# Galaxy.net
KiCad netlist of a schematic drawn in Altium Designer
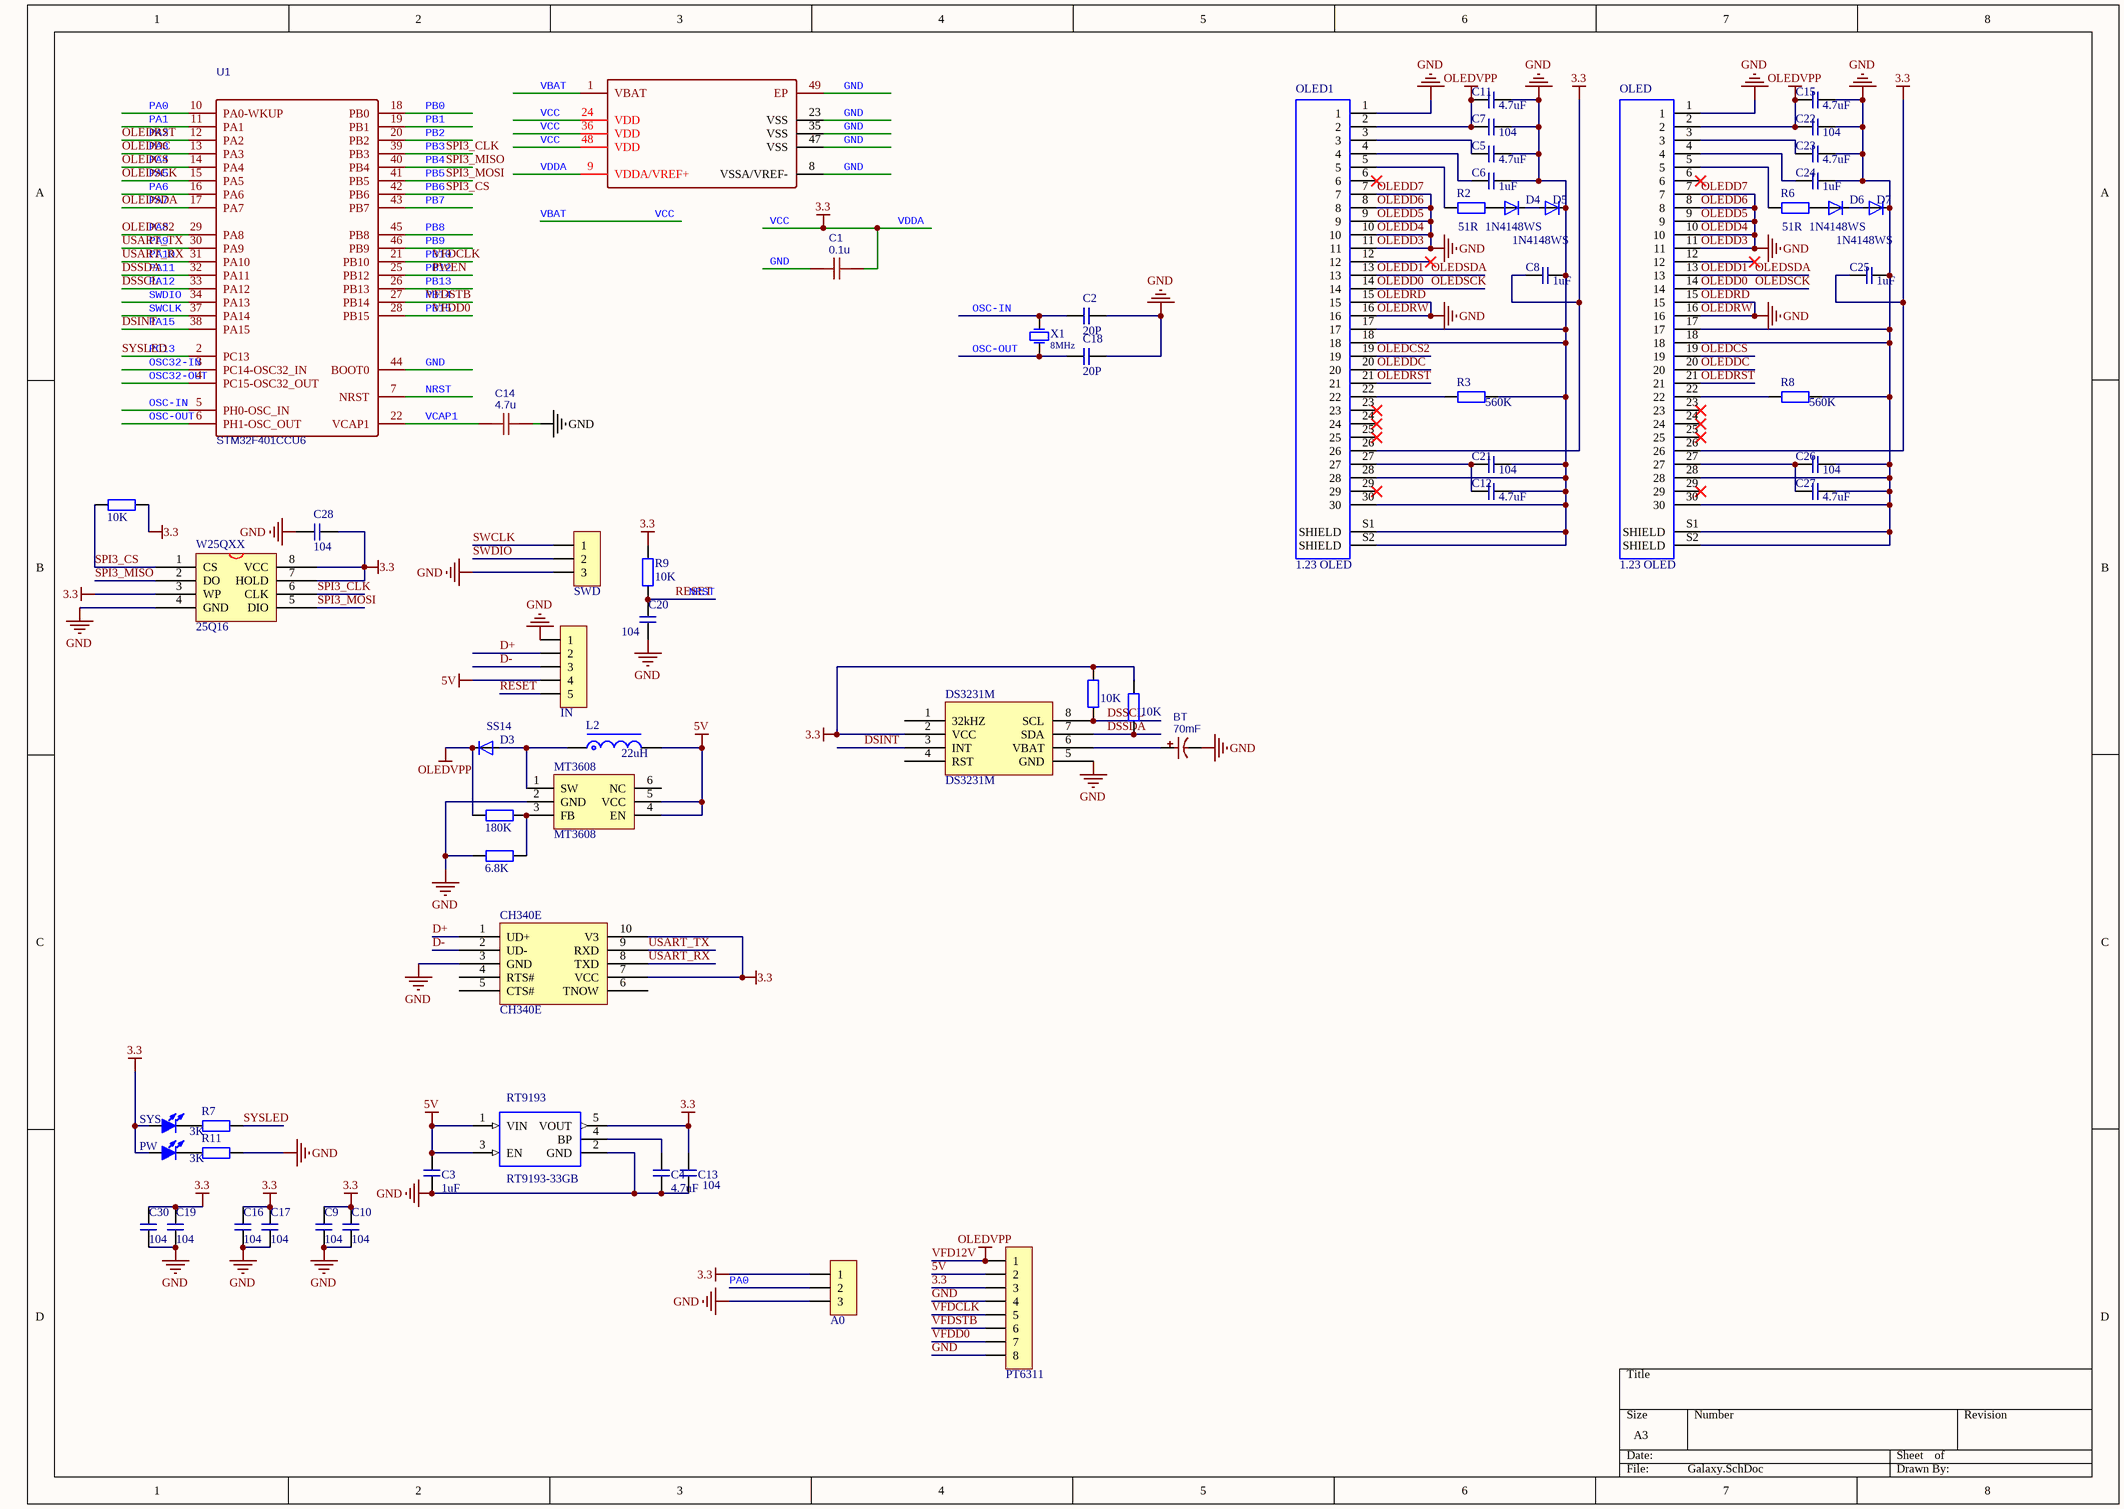
[diagram p0: Galaxy.SchDoc]

(export (version "E")
  (design (tool "Eeschema 10.0.6"))
  (components
    (comp (ref "A0")
      (value "HDR-1X3")
      (footprint "ZH1.5-WS-3P")
      (description "3P接插件")
      (fields (field (name "版权归属") "源创客"))
      (libsource (lib "4.3   - 接插件-脚距1.5") (part "Header 3"))
    )
    (comp (ref "BT")
      (value "70mF")
      (footprint "CAP-TH_BD4.8-P3.95_SM3R3703T01")
      (fields
        (field (name "BOM_SUPPLIER PART") "C132600")
        (field (name "BOM_MANUFACTURER PART") "SM3R3703T01")
        (field (name "CONTRIBUTOR") "LCSC")
      )
      (libsource (lib "altium-import") (part "root_0_70mF_"))
    )
    (comp (ref "C1")
      (value "0.1u")
      (footprint "0603C")
      (fields (field (name "CONTRIBUTOR") "LCEDA_Lib"))
      (libsource (lib "altium-import") (part "root_2_0.1u_"))
    )
    (comp (ref "C2") (value "20P") (footprint "0603C") (libsource (lib "Schlib1") (part "电容")))
    (comp (ref "C3") (value "1uF") (footprint "0603C") (libsource (lib "Schlib1") (part "电容")))
    (comp (ref "C4") (value "4.7uF") (footprint "0603C") (libsource (lib "Schlib1") (part "电容")))
    (comp (ref "C5") (value "4.7uF") (footprint "0603C") (libsource (lib "Schlib1") (part "电容")))
    (comp (ref "C6") (value "1uF") (footprint "0603C") (libsource (lib "Schlib1") (part "电容")))
    (comp (ref "C7") (value "104") (footprint "0603C") (libsource (lib "Schlib1") (part "电容")))
    (comp (ref "C8") (value "1uF") (footprint "0603C") (libsource (lib "Schlib1") (part "电容")))
    (comp (ref "C9") (value "104") (footprint "0603C") (libsource (lib "Schlib1") (part "电容")))
    (comp (ref "C10") (value "104") (footprint "0603C") (libsource (lib "Schlib1") (part "电容")))
    (comp (ref "C11") (value "4.7uF") (footprint "0603C") (libsource (lib "Schlib1") (part "电容")))
    (comp (ref "C12") (value "4.7uF") (footprint "0603C") (libsource (lib "Schlib1") (part "电容")))
    (comp (ref "C13") (value "104") (footprint "0603C") (libsource (lib "Schlib1") (part "电容")))
    (comp (ref "C14")
      (value "4.7u")
      (footprint "0603C")
      (fields (field (name "CONTRIBUTOR") "LCEDA_Lib"))
      (libsource (lib "altium-import") (part "root_0_4.7u_"))
    )
    (comp (ref "C15") (value "4.7uF") (footprint "0603C") (libsource (lib "Schlib1") (part "电容")))
    (comp (ref "C16") (value "104") (footprint "0603C") (libsource (lib "Schlib1") (part "电容")))
    (comp (ref "C17") (value "104") (footprint "0603C") (libsource (lib "Schlib1") (part "电容")))
    (comp (ref "C18") (value "20P") (footprint "0603C") (libsource (lib "Schlib1") (part "电容")))
    (comp (ref "C19") (value "104") (footprint "0603C") (libsource (lib "Schlib1") (part "电容")))
    (comp (ref "C20") (value "104") (footprint "0603C") (libsource (lib "Schlib1") (part "电容")))
    (comp (ref "C21") (value "104") (footprint "0603C") (libsource (lib "Schlib1") (part "电容")))
    (comp (ref "C22") (value "104") (footprint "0603C") (libsource (lib "Schlib1") (part "电容")))
    (comp (ref "C23") (value "4.7uF") (footprint "0603C") (libsource (lib "Schlib1") (part "电容")))
    (comp (ref "C24") (value "1uF") (footprint "0603C") (libsource (lib "Schlib1") (part "电容")))
    (comp (ref "C25") (value "1uF") (footprint "0603C") (libsource (lib "Schlib1") (part "电容")))
    (comp (ref "C26") (value "104") (footprint "0603C") (libsource (lib "Schlib1") (part "电容")))
    (comp (ref "C27") (value "4.7uF") (footprint "0603C") (libsource (lib "Schlib1") (part "电容")))
    (comp (ref "C28") (value "104") (footprint "0603C") (libsource (lib "") (part "电容_1")))
    (comp (ref "C30") (value "104") (footprint "0603C") (libsource (lib "Schlib1") (part "电容")))
    (comp (ref "CH340E") (value "CH340E") (footprint "MSOP10_L") (libsource (lib "CUBE_T1") (part "CH340E")))
    (comp (ref "D3")
      (value "SS14")
      (footprint "SOD323_1N4148WS")
      (description "Diode Switching 75V 0.3A 2-Pin SOD-323 T/R")
      (fields (field (name "MF") "ON Semiconductor") (field (name "MP") "1N4148WS"))
      (libsource (lib "1N4148WS") (part "1N4148WS"))
    )
    (comp (ref "D4")
      (value "1N4148WS")
      (footprint "SOD323_1N4148WS")
      (description "Diode Switching 75V 0.3A 2-Pin SOD-323 T/R")
      (fields (field (name "MF") "ON Semiconductor"))
      (libsource (lib "1N4148WS") (part "1N4148WS"))
    )
    (comp (ref "D5")
      (value "1N4148WS")
      (footprint "SOD323_1N4148WS")
      (description "Diode Switching 75V 0.3A 2-Pin SOD-323 T/R")
      (fields (field (name "MF") "ON Semiconductor"))
      (libsource (lib "1N4148WS") (part "1N4148WS"))
    )
    (comp (ref "D6")
      (value "1N4148WS")
      (footprint "SOD323_1N4148WS")
      (description "Diode Switching 75V 0.3A 2-Pin SOD-323 T/R")
      (fields (field (name "MF") "ON Semiconductor"))
      (libsource (lib "1N4148WS") (part "1N4148WS"))
    )
    (comp (ref "D7")
      (value "1N4148WS")
      (footprint "SOD323_1N4148WS")
      (description "Diode Switching 75V 0.3A 2-Pin SOD-323 T/R")
      (fields (field (name "MF") "ON Semiconductor"))
      (libsource (lib "1N4148WS") (part "1N4148WS"))
    )
    (comp (ref "DS3231M") (value "DS3231M") (footprint "SOP8") (libsource (lib "CUBE_T1") (part "DS3231M")))
    (comp (ref "IN")
      (value "HDR-1X5")
      (footprint "ZH1.5-WS-5P")
      (description "5P接插件")
      (fields (field (name "版权归属") "源创客"))
      (libsource (lib "4.3   - 接插件-脚距1.5") (part "Header 5"))
    )
    (comp (ref "L2")
      (value "22uH")
      (footprint "1210-ec")
      (description "功率屏蔽电感")
      (fields (field (name "版权归属") "源创客"))
      (libsource (lib "3.1   - 电阻-电容-电感") (part "L-CDRH"))
    )
    (comp (ref "MT3608")
      (value "MT3608")
      (footprint "SOT23-6N")
      (description "可调升压芯片")
      (fields (field (name "版权归属") "源创客"))
      (libsource (lib "1.3   - 电源类芯片") (part "SX1308"))
    )
    (comp (ref "OLED")
      (value "1.23 OLED")
      (footprint "1.23 OLED")
      (description "FH12 Series 30 Position 0.5 mm Pitch Surface Mount Right Angle Flip Lock FFC/FPC")
      (fields (field (name "MF") "Hirose Electric") (field (name "MP") "FH12-30S-0.5SH_55_"))
      (libsource (lib "Nebula") (part "FH12-30S-0.5SH(55)"))
    )
    (comp (ref "OLED1")
      (value "1.23 OLED")
      (footprint "1.23 OLED")
      (description "FH12 Series 30 Position 0.5 mm Pitch Surface Mount Right Angle Flip Lock FFC/FPC")
      (fields (field (name "MF") "Hirose Electric") (field (name "MP") "FH12-30S-0.5SH_55_"))
      (libsource (lib "Nebula") (part "FH12-30S-0.5SH(55)"))
    )
    (comp (ref "PT6311")
      (value "HDR-1X8")
      (footprint "ZH1.5-WS-8P")
      (description "8P接插件")
      (fields (field (name "版权归属") "源创客"))
      (libsource (lib "4.3   - 接插件-脚距1.5") (part "Header 8"))
    )
    (comp (ref "PW")
      (value "白色")
      (footprint "0603LED")
      (description "方形LED")
      (fields (field (name "版权归属") "源创客"))
      (libsource (lib "9.1   - LED") (part "LED-F234"))
    )
    (comp (ref "R2")
      (value "51R")
      (footprint "0603R")
      (description "贴片电阻")
      (fields (field (name "版权归属") "源创客"))
      (libsource (lib "3.1   - 电阻-电容-电感") (part "R"))
    )
    (comp (ref "R3")
      (value "560K")
      (footprint "0603R")
      (description "贴片电阻")
      (fields (field (name "版权归属") "源创客"))
      (libsource (lib "3.1   - 电阻-电容-电感") (part "R"))
    )
    (comp (ref "R4")
      (value "10K")
      (footprint "0603R")
      (description "贴片电阻")
      (fields (field (name "版权归属") "源创客"))
      (libsource (lib "3.1   - 电阻-电容-电感") (part "R"))
    )
    (comp (ref "R5")
      (value "10K")
      (footprint "0603R")
      (description "贴片电阻")
      (fields (field (name "版权归属") "源创客"))
      (libsource (lib "3.1   - 电阻-电容-电感") (part "R"))
    )
    (comp (ref "R6")
      (value "51R")
      (footprint "0603R")
      (description "贴片电阻")
      (fields (field (name "版权归属") "源创客"))
      (libsource (lib "3.1   - 电阻-电容-电感") (part "R"))
    )
    (comp (ref "R7")
      (value "3K")
      (footprint "0603R")
      (description "贴片电阻")
      (fields (field (name "版权归属") "源创客"))
      (libsource (lib "3.1   - 电阻-电容-电感") (part "R"))
    )
    (comp (ref "R8")
      (value "560K")
      (footprint "0603R")
      (description "贴片电阻")
      (fields (field (name "版权归属") "源创客"))
      (libsource (lib "3.1   - 电阻-电容-电感") (part "R"))
    )
    (comp (ref "R9")
      (value "10K")
      (footprint "0603R")
      (description "贴片电阻")
      (fields (field (name "版权归属") "源创客"))
      (libsource (lib "3.1   - 电阻-电容-电感") (part "R"))
    )
    (comp (ref "R10")
      (value "10K")
      (footprint "0603R")
      (description "贴片电阻")
      (fields (field (name "版权归属") "源创客"))
      (libsource (lib "3.1   - 电阻-电容-电感") (part "R"))
    )
    (comp (ref "R11")
      (value "3K")
      (footprint "0603R")
      (description "贴片电阻")
      (fields (field (name "版权归属") "源创客"))
      (libsource (lib "3.1   - 电阻-电容-电感") (part "R"))
    )
    (comp (ref "RB")
      (value "180K")
      (footprint "0603R")
      (description "贴片电阻")
      (fields (field (name "版权归属") "源创客"))
      (libsource (lib "3.1   - 电阻-电容-电感") (part "R"))
    )
    (comp (ref "RS")
      (value "6.8K")
      (footprint "0603R")
      (description "贴片电阻")
      (fields (field (name "版权归属") "源创客"))
      (libsource (lib "3.1   - 电阻-电容-电感") (part "R"))
    )
    (comp (ref "RT9193")
      (value "RT9193-33GB")
      (footprint "sot23-5")
      (description "RT9193 Series 300 mA 3.3 V Ultra-Low Noise Ultra-Fast CMOS LDO Regulator-SC-70-5")
      (fields (field (name "MF") "Richtek USA"))
      (libsource (lib "RT9193-33GB") (part "RT9193-33GB"))
    )
    (comp (ref "SWD")
      (value "HDR-1X3")
      (footprint "ZH1.5-WS-3P")
      (description "3P接插件")
      (fields (field (name "版权归属") "源创客"))
      (libsource (lib "4.3   - 接插件-脚距1.5") (part "Header 3"))
    )
    (comp (ref "SYS")
      (value "粉色")
      (footprint "0603LED")
      (description "方形LED")
      (fields (field (name "版权归属") "源创客"))
      (libsource (lib "9.1   - LED") (part "LED-F234"))
    )
    (comp (ref "U1")
      (value "STM32F401CCU6")
      (footprint "UFQFPN-48_L7.0-W7.0-P0.50-BL-EP")
      (fields (field (name "BOM_SUPPLIER PART") "C79861") (field (name "SUBPART_NO") "1"))
      (libsource (lib "Galaxy") (part "STM32F401CCU6"))
    )
    (comp (ref "W25QXX") (value "25Q16") (footprint "SOIC-8") (libsource (lib "Mark_7_1") (part "W25Q16")))
    (comp (ref "X1")
      (value "8MHz")
      (footprint "OSC 5032-2P")
      (description "XTAL,8MHz,±20PPM,12.6*4.5")
      (fields (field (name "Comment") "1.6.1.01.005.001"))
      (libsource (lib "Mark_7") (part "1.6.1.01.005.001"))
    )
  )
  (nets
    (net (code "1") (name "/D+") (class "Default")
      (node (ref "CH340E") (pin "1") (pinfunction "UD+_1") (pintype "passive"))
      (node (ref "IN") (pin "2") (pinfunction "2_2") (pintype "passive"))
    )
    (net (code "2") (name "/D-") (class "Default")
      (node (ref "CH340E") (pin "2") (pinfunction "UD-_2") (pintype "passive"))
      (node (ref "IN") (pin "3") (pinfunction "3_3") (pintype "passive"))
    )
    (net (code "3") (name "/DSINT") (class "Default")
      (node (ref "DS3231M") (pin "3") (pinfunction "INT_3") (pintype "passive"))
      (node (ref "U1") (pin "38") (pinfunction "PA15_38") (pintype "passive"))
    )
    (net (code "4") (name "/DSSCL") (class "Default")
      (node (ref "DS3231M") (pin "8") (pinfunction "SCL_8") (pintype "passive"))
      (node (ref "R10") (pin "2") (pinfunction "2_2") (pintype "passive"))
      (node (ref "U1") (pin "33") (pinfunction "PA12_33") (pintype "passive"))
    )
    (net (code "5") (name "/DSSDA") (class "Default")
      (node (ref "DS3231M") (pin "7") (pinfunction "SDA_7") (pintype "passive"))
      (node (ref "R4") (pin "2") (pinfunction "2_2") (pintype "passive"))
      (node (ref "U1") (pin "32") (pinfunction "PA11_32") (pintype "passive"))
    )
    (net (code "6") (name "/NRST") (class "Default")
      (node (ref "C20") (pin "1") (pinfunction "1_1") (pintype "passive"))
      (node (ref "IN") (pin "5") (pinfunction "5_5") (pintype "passive"))
      (node (ref "R9") (pin "2") (pinfunction "2_2") (pintype "passive"))
      (node (ref "U1") (pin "7") (pinfunction "NRST_7") (pintype "passive"))
    )
    (net (code "7") (name "/OLEDCS") (class "Default")
      (node (ref "OLED") (pin "19") (pinfunction "19_19") (pintype "passive"))
      (node (ref "U1") (pin "14") (pinfunction "PA4_14") (pintype "passive"))
    )
    (net (code "8") (name "/OLEDCS2") (class "Default")
      (node (ref "OLED1") (pin "19") (pinfunction "19_19") (pintype "passive"))
      (node (ref "U1") (pin "29") (pinfunction "PA8_29") (pintype "passive"))
    )
    (net (code "9") (name "/OLEDD0") (class "Default")
      (node (ref "OLED") (pin "14") (pinfunction "14_14") (pintype "passive"))
      (node (ref "OLED1") (pin "14") (pinfunction "14_14") (pintype "passive"))
      (node (ref "U1") (pin "15") (pinfunction "PA5_15") (pintype "passive"))
    )
    (net (code "10") (name "/OLEDD1") (class "Default")
      (node (ref "OLED") (pin "13") (pinfunction "13_13") (pintype "passive"))
      (node (ref "OLED1") (pin "13") (pinfunction "13_13") (pintype "passive"))
      (node (ref "U1") (pin "17") (pinfunction "PA7_17") (pintype "passive"))
    )
    (net (code "11") (name "/OLEDDC") (class "Default")
      (node (ref "OLED") (pin "20") (pinfunction "20_20") (pintype "passive"))
      (node (ref "OLED1") (pin "20") (pinfunction "20_20") (pintype "passive"))
      (node (ref "U1") (pin "13") (pinfunction "PA3_13") (pintype "passive"))
    )
    (net (code "12") (name "/OLEDRST") (class "Default")
      (node (ref "OLED") (pin "21") (pinfunction "21_21") (pintype "passive"))
      (node (ref "OLED1") (pin "21") (pinfunction "21_21") (pintype "passive"))
      (node (ref "U1") (pin "12") (pinfunction "PA2_12") (pintype "passive"))
    )
    (net (code "13") (name "/OSC-IN") (class "Default")
      (node (ref "C2") (pin "2") (pinfunction "2_2") (pintype "passive"))
      (node (ref "U1") (pin "5") (pinfunction "PH0-OSC_IN_5") (pintype "passive"))
      (node (ref "X1") (pin "1") (pinfunction "OSC1_1") (pintype "passive"))
    )
    (net (code "14") (name "/OSC-OUT") (class "Default")
      (node (ref "C18") (pin "2") (pinfunction "2_2") (pintype "passive"))
      (node (ref "U1") (pin "6") (pinfunction "PH1-OSC_OUT_6") (pintype "passive"))
      (node (ref "X1") (pin "2") (pinfunction "OSC2_2") (pintype "passive"))
    )
    (net (code "15") (name "/OSC32-IN") (class "Default")
      (node (ref "U1") (pin "3") (pinfunction "PC14-OSC32_IN_3") (pintype "passive"))
    )
    (net (code "16") (name "/OSC32-OUT") (class "Default")
      (node (ref "U1") (pin "4") (pinfunction "PC15-OSC32_OUT_4") (pintype "passive"))
    )
    (net (code "17") (name "/PA0") (class "Default")
      (node (ref "A0") (pin "2") (pinfunction "2_2") (pintype "passive"))
      (node (ref "U1") (pin "10") (pinfunction "PA0-WKUP_10") (pintype "passive"))
    )
    (net (code "18") (name "/PA1") (class "Default")
      (node (ref "U1") (pin "11") (pinfunction "PA1_11") (pintype "passive"))
    )
    (net (code "19") (name "/PA6") (class "Default")
      (node (ref "U1") (pin "16") (pinfunction "PA6_16") (pintype "passive"))
    )
    (net (code "20") (name "/PA9") (class "Default")
      (node (ref "CH340E") (pin "9") (pinfunction "RXD_9") (pintype "passive"))
      (node (ref "U1") (pin "30") (pinfunction "PA9_30") (pintype "passive"))
    )
    (net (code "21") (name "/PA10") (class "Default")
      (node (ref "CH340E") (pin "8") (pinfunction "TXD_8") (pintype "passive"))
      (node (ref "U1") (pin "31") (pinfunction "PA10_31") (pintype "passive"))
    )
    (net (code "22") (name "/PB0") (class "Default")
      (node (ref "U1") (pin "18") (pinfunction "PB0_18") (pintype "passive"))
    )
    (net (code "23") (name "/PB1") (class "Default")
      (node (ref "U1") (pin "19") (pinfunction "PB1_19") (pintype "passive"))
    )
    (net (code "24") (name "/PB2") (class "Default")
      (node (ref "U1") (pin "20") (pinfunction "PB2_20") (pintype "passive"))
    )
    (net (code "25") (name "/PB3") (class "Default")
      (node (ref "U1") (pin "39") (pinfunction "PB3_39") (pintype "passive"))
      (node (ref "W25QXX") (pin "6") (pinfunction "CLK_6") (pintype "passive"))
    )
    (net (code "26") (name "/PB4") (class "Default")
      (node (ref "U1") (pin "40") (pinfunction "PB4_40") (pintype "passive"))
      (node (ref "W25QXX") (pin "2") (pinfunction "DO_2") (pintype "passive"))
    )
    (net (code "27") (name "/PB5") (class "Default")
      (node (ref "U1") (pin "41") (pinfunction "PB5_41") (pintype "passive"))
      (node (ref "W25QXX") (pin "5") (pinfunction "DIO_5") (pintype "passive"))
    )
    (net (code "28") (name "/PB6") (class "Default")
      (node (ref "R5") (pin "1") (pinfunction "1_1") (pintype "passive"))
      (node (ref "U1") (pin "42") (pinfunction "PB6_42") (pintype "passive"))
      (node (ref "W25QXX") (pin "1") (pinfunction "CS_1") (pintype "passive"))
    )
    (net (code "29") (name "/PB7") (class "Default")
      (node (ref "U1") (pin "43") (pinfunction "PB7_43") (pintype "passive"))
    )
    (net (code "30") (name "/PB8") (class "Default")
      (node (ref "U1") (pin "45") (pinfunction "PB8_45") (pintype "passive"))
    )
    (net (code "31") (name "/PB9") (class "Default")
      (node (ref "U1") (pin "46") (pinfunction "PB9_46") (pintype "passive"))
    )
    (net (code "32") (name "/PB10") (class "Default")
      (node (ref "PT6311") (pin "5") (pinfunction "5_5") (pintype "passive"))
      (node (ref "U1") (pin "21") (pinfunction "PB10_21") (pintype "passive"))
    )
    (net (code "33") (name "/PB12") (class "Default")
      (node (ref "U1") (pin "25") (pinfunction "PB12_25") (pintype "passive"))
    )
    (net (code "34") (name "/PB13") (class "Default")
      (node (ref "U1") (pin "26") (pinfunction "PB13_26") (pintype "passive"))
    )
    (net (code "35") (name "/PB14") (class "Default")
      (node (ref "PT6311") (pin "6") (pinfunction "6_6") (pintype "passive"))
      (node (ref "U1") (pin "27") (pinfunction "PB14_27") (pintype "passive"))
    )
    (net (code "36") (name "/PB15") (class "Default")
      (node (ref "PT6311") (pin "7") (pinfunction "7_7") (pintype "passive"))
      (node (ref "U1") (pin "28") (pinfunction "PB15_28") (pintype "passive"))
    )
    (net (code "37") (name "/PC13") (class "Default")
      (node (ref "R7") (pin "1") (pinfunction "1_1") (pintype "passive"))
      (node (ref "U1") (pin "2") (pinfunction "PC13_2") (pintype "passive"))
    )
    (net (code "38") (name "/SWCLK") (class "Default")
      (node (ref "SWD") (pin "1") (pinfunction "1_1") (pintype "passive"))
      (node (ref "U1") (pin "37") (pinfunction "PA14_37") (pintype "passive"))
    )
    (net (code "39") (name "/SWDIO") (class "Default")
      (node (ref "SWD") (pin "2") (pinfunction "2_2") (pintype "passive"))
      (node (ref "U1") (pin "34") (pinfunction "PA13_34") (pintype "passive"))
    )
    (net (code "40") (name "/VCAP1") (class "Default")
      (node (ref "C14") (pin "1") (pinfunction "1_1") (pintype "passive"))
      (node (ref "U1") (pin "22") (pinfunction "VCAP1_22") (pintype "passive"))
    )
    (net (code "41") (name "3.3") (class "Default")
      (node (ref "A0") (pin "1") (pinfunction "1_1") (pintype "passive"))
      (node (ref "C1") (pin "1") (pinfunction "1_1") (pintype "passive"))
      (node (ref "C10") (pin "1") (pinfunction "1_1") (pintype "passive"))
      (node (ref "C13") (pin "2") (pinfunction "2_2") (pintype "passive"))
      (node (ref "C16") (pin "1") (pinfunction "1_1") (pintype "passive"))
      (node (ref "C17") (pin "1") (pinfunction "1_1") (pintype "passive"))
      (node (ref "C19") (pin "1") (pinfunction "1_1") (pintype "passive"))
      (node (ref "C25") (pin "1") (pinfunction "1_1") (pintype "passive"))
      (node (ref "C28") (pin "2") (pinfunction "2_2") (pintype "passive"))
      (node (ref "C30") (pin "1") (pinfunction "1_1") (pintype "passive"))
      (node (ref "C8") (pin "1") (pinfunction "1_1") (pintype "passive"))
      (node (ref "C9") (pin "1") (pinfunction "1_1") (pintype "passive"))
      (node (ref "CH340E") (pin "10") (pinfunction "V3_10") (pintype "passive"))
      (node (ref "CH340E") (pin "7") (pinfunction "VCC_7") (pintype "passive"))
      (node (ref "DS3231M") (pin "2") (pinfunction "VCC_2") (pintype "passive"))
      (node (ref "OLED") (pin "26") (pinfunction "26_26") (pintype "passive"))
      (node (ref "OLED1") (pin "26") (pinfunction "26_26") (pintype "passive"))
      (node (ref "PT6311") (pin "3") (pinfunction "3_3") (pintype "passive"))
      (node (ref "PW") (pin "1") (pinfunction "A_1") (pintype "passive"))
      (node (ref "R10") (pin "1") (pinfunction "1_1") (pintype "passive"))
      (node (ref "R4") (pin "1") (pinfunction "1_1") (pintype "passive"))
      (node (ref "R5") (pin "2") (pinfunction "2_2") (pintype "passive"))
      (node (ref "R9") (pin "1") (pinfunction "1_1") (pintype "passive"))
      (node (ref "RT9193") (pin "5") (pinfunction "VOUT_5") (pintype "output"))
      (node (ref "SYS") (pin "1") (pinfunction "A_1") (pintype "passive"))
      (node (ref "U1") (pin "1") (pinfunction "VBAT_1") (pintype "passive"))
      (node (ref "U1") (pin "24") (pinfunction "VDD_24") (pintype "passive"))
      (node (ref "U1") (pin "36") (pinfunction "VDD_36") (pintype "passive"))
      (node (ref "U1") (pin "48") (pinfunction "VDD_48") (pintype "passive"))
      (node (ref "U1") (pin "9") (pinfunction "VDDA/VREF+_9") (pintype "passive"))
      (node (ref "W25QXX") (pin "3") (pinfunction "WP_3") (pintype "passive"))
      (node (ref "W25QXX") (pin "7") (pinfunction "HOLD_7") (pintype "passive"))
      (node (ref "W25QXX") (pin "8") (pinfunction "VCC_8") (pintype "passive"))
    )
    (net (code "42") (name "5V") (class "Default")
      (node (ref "C3") (pin "2") (pinfunction "2_2") (pintype "passive"))
      (node (ref "IN") (pin "4") (pinfunction "4_4") (pintype "passive"))
      (node (ref "L2") (pin "2") (pinfunction "2_2") (pintype "passive"))
      (node (ref "MT3608") (pin "4") (pinfunction "EN_4") (pintype "passive"))
      (node (ref "MT3608") (pin "5") (pinfunction "VCC_5") (pintype "passive"))
      (node (ref "PT6311") (pin "2") (pinfunction "2_2") (pintype "passive"))
      (node (ref "RT9193") (pin "1") (pinfunction "VIN_1") (pintype "input"))
      (node (ref "RT9193") (pin "3") (pinfunction "EN_3") (pintype "input"))
    )
    (net (code "43") (name "GND") (class "Default")
      (node (ref "A0") (pin "3") (pinfunction "3_3") (pintype "passive"))
      (node (ref "BT") (pin "2") (pinfunction "2_2") (pintype "passive"))
      (node (ref "C1") (pin "2") (pinfunction "2_2") (pintype "passive"))
      (node (ref "C10") (pin "2") (pinfunction "2_2") (pintype "passive"))
      (node (ref "C11") (pin "2") (pinfunction "2_2") (pintype "passive"))
      (node (ref "C12") (pin "2") (pinfunction "2_2") (pintype "passive"))
      (node (ref "C13") (pin "1") (pinfunction "1_1") (pintype "passive"))
      (node (ref "C14") (pin "2") (pinfunction "2_2") (pintype "passive"))
      (node (ref "C15") (pin "2") (pinfunction "2_2") (pintype "passive"))
      (node (ref "C16") (pin "2") (pinfunction "2_2") (pintype "passive"))
      (node (ref "C17") (pin "2") (pinfunction "2_2") (pintype "passive"))
      (node (ref "C18") (pin "1") (pinfunction "1_1") (pintype "passive"))
      (node (ref "C19") (pin "2") (pinfunction "2_2") (pintype "passive"))
      (node (ref "C2") (pin "1") (pinfunction "1_1") (pintype "passive"))
      (node (ref "C20") (pin "2") (pinfunction "2_2") (pintype "passive"))
      (node (ref "C21") (pin "2") (pinfunction "2_2") (pintype "passive"))
      (node (ref "C22") (pin "2") (pinfunction "2_2") (pintype "passive"))
      (node (ref "C23") (pin "2") (pinfunction "2_2") (pintype "passive"))
      (node (ref "C24") (pin "2") (pinfunction "2_2") (pintype "passive"))
      (node (ref "C25") (pin "2") (pinfunction "2_2") (pintype "passive"))
      (node (ref "C26") (pin "2") (pinfunction "2_2") (pintype "passive"))
      (node (ref "C27") (pin "2") (pinfunction "2_2") (pintype "passive"))
      (node (ref "C28") (pin "1") (pinfunction "1_1") (pintype "passive"))
      (node (ref "C3") (pin "1") (pinfunction "1_1") (pintype "passive"))
      (node (ref "C30") (pin "2") (pinfunction "2_2") (pintype "passive"))
      (node (ref "C4") (pin "1") (pinfunction "1_1") (pintype "passive"))
      (node (ref "C5") (pin "2") (pinfunction "2_2") (pintype "passive"))
      (node (ref "C6") (pin "2") (pinfunction "2_2") (pintype "passive"))
      (node (ref "C7") (pin "2") (pinfunction "2_2") (pintype "passive"))
      (node (ref "C8") (pin "2") (pinfunction "2_2") (pintype "passive"))
      (node (ref "C9") (pin "2") (pinfunction "2_2") (pintype "passive"))
      (node (ref "CH340E") (pin "3") (pinfunction "GND_3") (pintype "passive"))
      (node (ref "D5") (pin "C") (pinfunction "C_C") (pintype "passive"))
      (node (ref "D7") (pin "C") (pinfunction "C_C") (pintype "passive"))
      (node (ref "DS3231M") (pin "5") (pinfunction "GND_5") (pintype "passive"))
      (node (ref "IN") (pin "1") (pinfunction "1_1") (pintype "passive"))
      (node (ref "MT3608") (pin "2") (pinfunction "GND_2") (pintype "passive"))
      (node (ref "OLED") (pin "1") (pinfunction "1_1") (pintype "passive"))
      (node (ref "OLED") (pin "10") (pinfunction "10_10") (pintype "passive"))
      (node (ref "OLED") (pin "11") (pinfunction "11_11") (pintype "passive"))
      (node (ref "OLED") (pin "15") (pinfunction "15_15") (pintype "passive"))
      (node (ref "OLED") (pin "16") (pinfunction "16_16") (pintype "passive"))
      (node (ref "OLED") (pin "17") (pinfunction "17_17") (pintype "passive"))
      (node (ref "OLED") (pin "18") (pinfunction "18_18") (pintype "passive"))
      (node (ref "OLED") (pin "28") (pinfunction "28_28") (pintype "passive"))
      (node (ref "OLED") (pin "30") (pinfunction "30_30") (pintype "passive"))
      (node (ref "OLED") (pin "7") (pinfunction "7_7") (pintype "passive"))
      (node (ref "OLED") (pin "8") (pinfunction "8_8") (pintype "passive"))
      (node (ref "OLED") (pin "9") (pinfunction "9_9") (pintype "passive"))
      (node (ref "OLED") (pin "S1") (pinfunction "SHIELD_S1") (pintype "passive"))
      (node (ref "OLED") (pin "S2") (pinfunction "SHIELD_S2") (pintype "passive"))
      (node (ref "OLED1") (pin "1") (pinfunction "1_1") (pintype "passive"))
      (node (ref "OLED1") (pin "10") (pinfunction "10_10") (pintype "passive"))
      (node (ref "OLED1") (pin "11") (pinfunction "11_11") (pintype "passive"))
      (node (ref "OLED1") (pin "15") (pinfunction "15_15") (pintype "passive"))
      (node (ref "OLED1") (pin "16") (pinfunction "16_16") (pintype "passive"))
      (node (ref "OLED1") (pin "17") (pinfunction "17_17") (pintype "passive"))
      (node (ref "OLED1") (pin "18") (pinfunction "18_18") (pintype "passive"))
      (node (ref "OLED1") (pin "28") (pinfunction "28_28") (pintype "passive"))
      (node (ref "OLED1") (pin "30") (pinfunction "30_30") (pintype "passive"))
      (node (ref "OLED1") (pin "7") (pinfunction "7_7") (pintype "passive"))
      (node (ref "OLED1") (pin "8") (pinfunction "8_8") (pintype "passive"))
      (node (ref "OLED1") (pin "9") (pinfunction "9_9") (pintype "passive"))
      (node (ref "OLED1") (pin "S1") (pinfunction "SHIELD_S1") (pintype "passive"))
      (node (ref "OLED1") (pin "S2") (pinfunction "SHIELD_S2") (pintype "passive"))
      (node (ref "PT6311") (pin "4") (pinfunction "4_4") (pintype "passive"))
      (node (ref "PT6311") (pin "8") (pinfunction "8_8") (pintype "passive"))
      (node (ref "R11") (pin "1") (pinfunction "1_1") (pintype "passive"))
      (node (ref "R3") (pin "1") (pinfunction "1_1") (pintype "passive"))
      (node (ref "R8") (pin "1") (pinfunction "1_1") (pintype "passive"))
      (node (ref "RS") (pin "1") (pinfunction "1_1") (pintype "passive"))
      (node (ref "RT9193") (pin "2") (pinfunction "GND_2") (pintype "power_in"))
      (node (ref "SWD") (pin "3") (pinfunction "3_3") (pintype "passive"))
      (node (ref "U1") (pin "23") (pinfunction "VSS_23") (pintype "passive"))
      (node (ref "U1") (pin "35") (pinfunction "VSS_35") (pintype "passive"))
      (node (ref "U1") (pin "44") (pinfunction "BOOT0_44") (pintype "passive"))
      (node (ref "U1") (pin "47") (pinfunction "VSS_47") (pintype "passive"))
      (node (ref "U1") (pin "49") (pinfunction "EP_49") (pintype "passive"))
      (node (ref "U1") (pin "8") (pinfunction "VSSA/VREF-_8") (pintype "passive"))
      (node (ref "W25QXX") (pin "4") (pinfunction "GND_4") (pintype "passive"))
    )
    (net (code "44") (name "Net-(C5-Pad1)") (class "Default")
      (node (ref "C5") (pin "1") (pinfunction "1_1") (pintype "passive"))
      (node (ref "OLED1") (pin "3") (pinfunction "3_3") (pintype "passive"))
    )
    (net (code "45") (name "Net-(C6-Pad1)") (class "Default")
      (node (ref "C6") (pin "1") (pinfunction "1_1") (pintype "passive"))
      (node (ref "OLED1") (pin "4") (pinfunction "4_4") (pintype "passive"))
    )
    (net (code "46") (name "Net-(C12-Pad1)") (class "Default")
      (node (ref "C12") (pin "1") (pinfunction "1_1") (pintype "passive"))
      (node (ref "C21") (pin "1") (pinfunction "1_1") (pintype "passive"))
      (node (ref "OLED1") (pin "27") (pinfunction "27_27") (pintype "passive"))
    )
    (net (code "47") (name "Net-(C23-Pad1)") (class "Default")
      (node (ref "C23") (pin "1") (pinfunction "1_1") (pintype "passive"))
      (node (ref "OLED") (pin "3") (pinfunction "3_3") (pintype "passive"))
    )
    (net (code "48") (name "Net-(C24-Pad1)") (class "Default")
      (node (ref "C24") (pin "1") (pinfunction "1_1") (pintype "passive"))
      (node (ref "OLED") (pin "4") (pinfunction "4_4") (pintype "passive"))
    )
    (net (code "49") (name "Net-(C26-Pad1)") (class "Default")
      (node (ref "C26") (pin "1") (pinfunction "1_1") (pintype "passive"))
      (node (ref "C27") (pin "1") (pinfunction "1_1") (pintype "passive"))
      (node (ref "OLED") (pin "27") (pinfunction "27_27") (pintype "passive"))
    )
    (net (code "50") (name "Net-(D4-PadA)") (class "Default")
      (node (ref "D4") (pin "A") (pinfunction "A_A") (pintype "passive"))
      (node (ref "R2") (pin "1") (pinfunction "1_1") (pintype "passive"))
    )
    (net (code "51") (name "Net-(D4-PadC)") (class "Default")
      (node (ref "D4") (pin "C") (pinfunction "C_C") (pintype "passive"))
      (node (ref "D5") (pin "A") (pinfunction "A_A") (pintype "passive"))
    )
    (net (code "52") (name "Net-(D6-PadA)") (class "Default")
      (node (ref "D6") (pin "A") (pinfunction "A_A") (pintype "passive"))
      (node (ref "R6") (pin "1") (pinfunction "1_1") (pintype "passive"))
    )
    (net (code "53") (name "Net-(D6-PadC)") (class "Default")
      (node (ref "D6") (pin "C") (pinfunction "C_C") (pintype "passive"))
      (node (ref "D7") (pin "A") (pinfunction "A_A") (pintype "passive"))
    )
    (net (code "54") (name "Net-(DS3231M-VBAT)") (class "Default")
      (node (ref "BT") (pin "1") (pinfunction "1_1") (pintype "passive"))
      (node (ref "DS3231M") (pin "6") (pinfunction "VBAT_6") (pintype "passive"))
    )
    (net (code "55") (name "Net-(MT3608-FB)") (class "Default")
      (node (ref "MT3608") (pin "3") (pinfunction "FB_3") (pintype "passive"))
      (node (ref "RB") (pin "2") (pinfunction "2_2") (pintype "passive"))
      (node (ref "RS") (pin "2") (pinfunction "2_2") (pintype "passive"))
    )
    (net (code "56") (name "Net-(MT3608-SW)") (class "Default")
      (node (ref "D3") (pin "A") (pinfunction "A_A") (pintype "passive"))
      (node (ref "L2") (pin "1") (pinfunction "1_1") (pintype "passive"))
      (node (ref "MT3608") (pin "1") (pinfunction "SW_1") (pintype "passive"))
    )
    (net (code "57") (name "Net-(OLED-Pad5)") (class "Default")
      (node (ref "OLED") (pin "5") (pinfunction "5_5") (pintype "passive"))
      (node (ref "R6") (pin "2") (pinfunction "2_2") (pintype "passive"))
    )
    (net (code "58") (name "Net-(OLED-Pad22)") (class "Default")
      (node (ref "OLED") (pin "22") (pinfunction "22_22") (pintype "passive"))
      (node (ref "R8") (pin "2") (pinfunction "2_2") (pintype "passive"))
    )
    (net (code "59") (name "Net-(OLED1-Pad5)") (class "Default")
      (node (ref "OLED1") (pin "5") (pinfunction "5_5") (pintype "passive"))
      (node (ref "R2") (pin "2") (pinfunction "2_2") (pintype "passive"))
    )
    (net (code "60") (name "Net-(OLED1-Pad22)") (class "Default")
      (node (ref "OLED1") (pin "22") (pinfunction "22_22") (pintype "passive"))
      (node (ref "R3") (pin "2") (pinfunction "2_2") (pintype "passive"))
    )
    (net (code "61") (name "Net-(PW-K)") (class "Default")
      (node (ref "PW") (pin "2") (pinfunction "K_2") (pintype "passive"))
      (node (ref "R11") (pin "2") (pinfunction "2_2") (pintype "passive"))
    )
    (net (code "62") (name "Net-(RT9193-BP)") (class "Default")
      (node (ref "C4") (pin "2") (pinfunction "2_2") (pintype "passive"))
      (node (ref "RT9193") (pin "4") (pinfunction "BP_4") (pintype "passive"))
    )
    (net (code "63") (name "Net-(SYS-K)") (class "Default")
      (node (ref "R7") (pin "2") (pinfunction "2_2") (pintype "passive"))
      (node (ref "SYS") (pin "2") (pinfunction "K_2") (pintype "passive"))
    )
    (net (code "64") (name "OLEDVPP") (class "Default")
      (node (ref "C11") (pin "1") (pinfunction "1_1") (pintype "passive"))
      (node (ref "C15") (pin "1") (pinfunction "1_1") (pintype "passive"))
      (node (ref "C22") (pin "1") (pinfunction "1_1") (pintype "passive"))
      (node (ref "C7") (pin "1") (pinfunction "1_1") (pintype "passive"))
      (node (ref "D3") (pin "C") (pinfunction "C_C") (pintype "passive"))
      (node (ref "OLED") (pin "2") (pinfunction "2_2") (pintype "passive"))
      (node (ref "OLED1") (pin "2") (pinfunction "2_2") (pintype "passive"))
      (node (ref "PT6311") (pin "1") (pinfunction "1_1") (pintype "passive"))
      (node (ref "RB") (pin "1") (pinfunction "1_1") (pintype "passive"))
    )
    (net (code "65") (name "unconnected-(CH340E-CTS#-Pad5)") (class "Default")
      (node (ref "CH340E") (pin "5") (pinfunction "CTS#_5") (pintype "passive"))
    )
    (net (code "66") (name "unconnected-(CH340E-RTS#-Pad4)") (class "Default")
      (node (ref "CH340E") (pin "4") (pinfunction "RTS#_4") (pintype "passive"))
    )
    (net (code "67") (name "unconnected-(CH340E-TNOW-Pad6)") (class "Default")
      (node (ref "CH340E") (pin "6") (pinfunction "TNOW_6") (pintype "passive"))
    )
    (net (code "68") (name "unconnected-(DS3231M-32kHZ-Pad1)") (class "Default")
      (node (ref "DS3231M") (pin "1") (pinfunction "32kHZ_1") (pintype "passive"))
    )
    (net (code "69") (name "unconnected-(DS3231M-RST-Pad4)") (class "Default")
      (node (ref "DS3231M") (pin "4") (pinfunction "RST_4") (pintype "passive"))
    )
    (net (code "70") (name "unconnected-(MT3608-NC-Pad6)") (class "Default")
      (node (ref "MT3608") (pin "6") (pinfunction "NC_6") (pintype "passive"))
    )
    (net (code "71") (name "unconnected-(OLED-Pad6)") (class "Default")
      (node (ref "OLED") (pin "6") (pinfunction "6_6") (pintype "passive+no_connect"))
    )
    (net (code "72") (name "unconnected-(OLED-Pad12)") (class "Default")
      (node (ref "OLED") (pin "12") (pinfunction "12_12") (pintype "passive+no_connect"))
    )
    (net (code "73") (name "unconnected-(OLED-Pad23)") (class "Default")
      (node (ref "OLED") (pin "23") (pinfunction "23_23") (pintype "passive+no_connect"))
    )
    (net (code "74") (name "unconnected-(OLED-Pad24)") (class "Default")
      (node (ref "OLED") (pin "24") (pinfunction "24_24") (pintype "passive+no_connect"))
    )
    (net (code "75") (name "unconnected-(OLED-Pad25)") (class "Default")
      (node (ref "OLED") (pin "25") (pinfunction "25_25") (pintype "passive+no_connect"))
    )
    (net (code "76") (name "unconnected-(OLED-Pad29)") (class "Default")
      (node (ref "OLED") (pin "29") (pinfunction "29_29") (pintype "passive+no_connect"))
    )
    (net (code "77") (name "unconnected-(OLED1-Pad6)") (class "Default")
      (node (ref "OLED1") (pin "6") (pinfunction "6_6") (pintype "passive+no_connect"))
    )
    (net (code "78") (name "unconnected-(OLED1-Pad12)") (class "Default")
      (node (ref "OLED1") (pin "12") (pinfunction "12_12") (pintype "passive+no_connect"))
    )
    (net (code "79") (name "unconnected-(OLED1-Pad23)") (class "Default")
      (node (ref "OLED1") (pin "23") (pinfunction "23_23") (pintype "passive+no_connect"))
    )
    (net (code "80") (name "unconnected-(OLED1-Pad24)") (class "Default")
      (node (ref "OLED1") (pin "24") (pinfunction "24_24") (pintype "passive+no_connect"))
    )
    (net (code "81") (name "unconnected-(OLED1-Pad25)") (class "Default")
      (node (ref "OLED1") (pin "25") (pinfunction "25_25") (pintype "passive+no_connect"))
    )
    (net (code "82") (name "unconnected-(OLED1-Pad29)") (class "Default")
      (node (ref "OLED1") (pin "29") (pinfunction "29_29") (pintype "passive+no_connect"))
    )
  )
)
